# simple-loop-active4.net
KiCad netlist of a schematic drawn in EAGLE
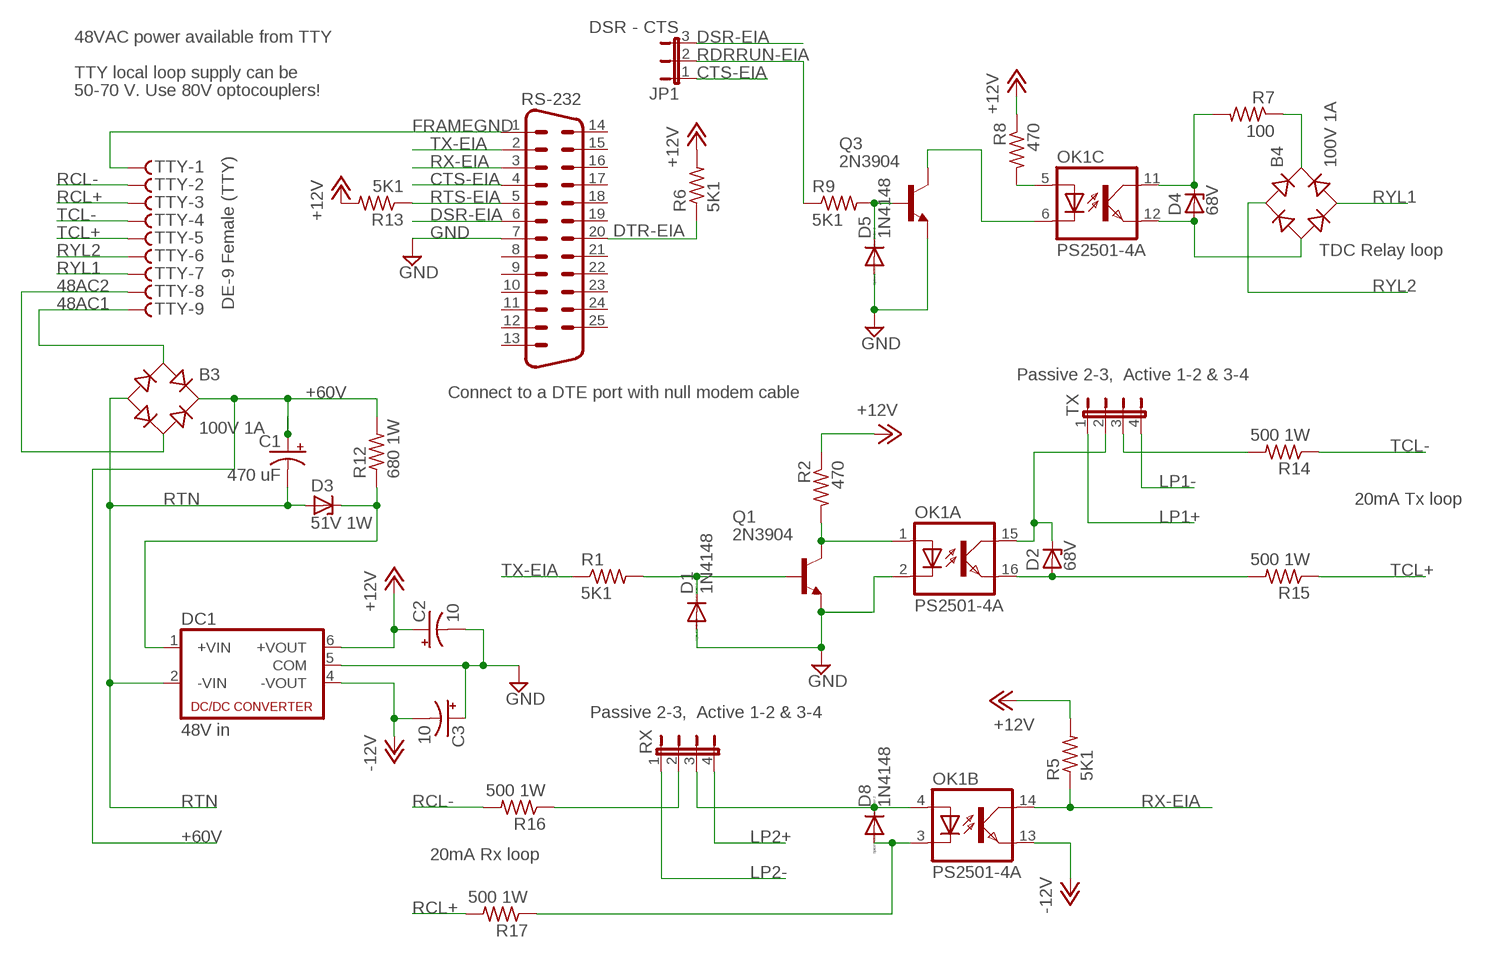
[diagram p0: schematic, sheet 1]
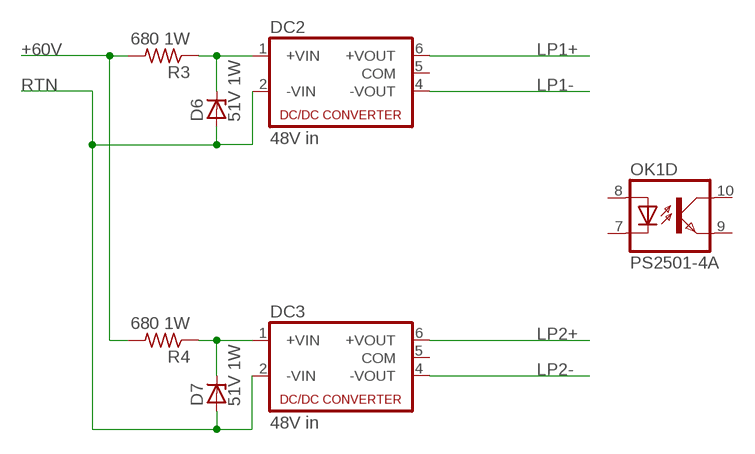
[diagram p1: schematic, sheet 2]

(export (version "E")
  (design (tool "Eeschema 10.0.6"))
  (components
    (comp (ref "D6")
      (value "51V 1W")
      (footprint "eagle-import:DO41Z10")
      (libsource (lib "eagle-import") (part "ZENER-DIODEDO41Z10"))
    )
    (comp (ref "D7")
      (value "51V 1W")
      (footprint "eagle-import:DO41Z10")
      (libsource (lib "eagle-import") (part "ZENER-DIODEDO41Z10"))
    )
    (comp (ref "DC2")
      (value "48V in")
      (footprint "eagle-import:NMA")
      (fields (field (name "MF") "C & D TECHNOLOGIES, INC") (field (name "MPN") "NMA0515SC"))
      (libsource (lib "eagle-import") (part "NMA"))
    )
    (comp (ref "DC3")
      (value "48V in")
      (footprint "eagle-import:NMA")
      (fields (field (name "MF") "C & D TECHNOLOGIES, INC") (field (name "MPN") "NMA0515SC"))
      (libsource (lib "eagle-import") (part "NMA"))
    )
    (comp (ref "OK1")
      (value "PS2501-4A")
      (footprint "eagle-import:DIL16")
      (fields (field (name "MF") "VISHAY/TELEFUNKEN") (field (name "MPN") "ILQ1"))
      (libsource (lib "eagle-import") (part "ILQ1"))
    )
    (comp (ref "R3")
      (value "680 1W")
      (footprint "eagle-import:P0817V")
      (libsource (lib "eagle-import") (part "R-US_0817/7V"))
    )
    (comp (ref "R4")
      (value "680 1W")
      (footprint "eagle-import:P0817V")
      (libsource (lib "eagle-import") (part "R-US_0817/7V"))
    )
    (comp (ref "B3")
      (value "100V 1A")
      (footprint "eagle-import:RB1A")
      (libsource (lib "eagle-import") (part "RB1A"))
    )
    (comp (ref "B4")
      (value "100V 1A")
      (footprint "eagle-import:RB1A")
      (libsource (lib "eagle-import") (part "RB1A"))
    )
    (comp (ref "C1")
      (value "470 uF")
      (footprint "eagle-import:E7,5-18")
      (libsource (lib "eagle-import") (part "CPOL-USE7.5-18"))
    )
    (comp (ref "C2")
      (value "10")
      (footprint "eagle-import:B45181A")
      (libsource (lib "eagle-import") (part "CPOL-USB45181A"))
    )
    (comp (ref "C3")
      (value "10")
      (footprint "eagle-import:B45181A")
      (libsource (lib "eagle-import") (part "CPOL-USB45181A"))
    )
    (comp (ref "D1")
      (value "1N4148")
      (footprint "eagle-import:DO35-10")
      (libsource (lib "eagle-import") (part "1N4148DO35-10"))
    )
    (comp (ref "D2")
      (value "68V")
      (footprint "eagle-import:DO41Z10")
      (libsource (lib "eagle-import") (part "ZENER-DIODEDO41Z10"))
    )
    (comp (ref "D3")
      (value "51V 1W")
      (footprint "eagle-import:DO41Z10")
      (libsource (lib "eagle-import") (part "ZENER-DIODEDO41Z10"))
    )
    (comp (ref "D4")
      (value "68V")
      (footprint "eagle-import:DO41Z10")
      (libsource (lib "eagle-import") (part "ZENER-DIODEDO41Z10"))
    )
    (comp (ref "D5")
      (value "1N4148")
      (footprint "eagle-import:DO35-10")
      (libsource (lib "eagle-import") (part "1N4148DO35-10"))
    )
    (comp (ref "D8")
      (value "1N4148")
      (footprint "eagle-import:DO35-10")
      (libsource (lib "eagle-import") (part "1N4148DO35-10"))
    )
    (comp (ref "DC1")
      (value "48V in")
      (footprint "eagle-import:NMA")
      (fields (field (name "MF") "C & D TECHNOLOGIES, INC") (field (name "MPN") "NMA0515SC"))
      (libsource (lib "eagle-import") (part "NMA"))
    )
    (comp (ref "JP1")
      (value "DSR - CTS")
      (footprint "eagle-import:JP2")
      (libsource (lib "eagle-import") (part "JP2E"))
    )
    (comp (ref "Q1")
      (value "2N3904")
      (footprint "eagle-import:TO92")
      (libsource (lib "eagle-import") (part "2N3904"))
    )
    (comp (ref "Q3")
      (value "2N3904")
      (footprint "eagle-import:TO92")
      (libsource (lib "eagle-import") (part "2N3904"))
    )
    (comp (ref "R1")
      (value "5K1")
      (footprint "eagle-import:0207_10")
      (libsource (lib "eagle-import") (part "R-US_0207/10"))
    )
    (comp (ref "R2")
      (value "470")
      (footprint "eagle-import:0207_10")
      (libsource (lib "eagle-import") (part "R-US_0207/10"))
    )
    (comp (ref "R5")
      (value "5K1")
      (footprint "eagle-import:0207_10")
      (libsource (lib "eagle-import") (part "R-US_0207/10"))
    )
    (comp (ref "R6")
      (value "5K1")
      (footprint "eagle-import:0207_10")
      (libsource (lib "eagle-import") (part "R-US_0207/10"))
    )
    (comp (ref "R7")
      (value "100")
      (footprint "eagle-import:0207_10")
      (libsource (lib "eagle-import") (part "R-US_0207/10"))
    )
    (comp (ref "R8")
      (value "470")
      (footprint "eagle-import:0207_10")
      (libsource (lib "eagle-import") (part "R-US_0207/10"))
    )
    (comp (ref "R9")
      (value "5K1")
      (footprint "eagle-import:0207_10")
      (libsource (lib "eagle-import") (part "R-US_0207/10"))
    )
    (comp (ref "R12")
      (value "680 1W")
      (footprint "eagle-import:P0817V")
      (libsource (lib "eagle-import") (part "R-US_0817/7V"))
    )
    (comp (ref "R13")
      (value "5K1")
      (footprint "eagle-import:0207_10")
      (libsource (lib "eagle-import") (part "R-US_0207/10"))
    )
    (comp (ref "R14")
      (value "500 1W")
      (footprint "eagle-import:P0817V")
      (libsource (lib "eagle-import") (part "R-US_0817/7V"))
    )
    (comp (ref "R15")
      (value "500 1W")
      (footprint "eagle-import:P0817V")
      (libsource (lib "eagle-import") (part "R-US_0817/7V"))
    )
    (comp (ref "R16")
      (value "500 1W")
      (footprint "eagle-import:P0817V")
      (libsource (lib "eagle-import") (part "R-US_0817/7V"))
    )
    (comp (ref "R17")
      (value "500 1W")
      (footprint "eagle-import:P0817V")
      (libsource (lib "eagle-import") (part "R-US_0817/7V"))
    )
    (comp (ref "RS-232")
      (value "M25H")
      (footprint "eagle-import:M25H")
      (libsource (lib "eagle-import") (part "M25H"))
    )
    (comp (ref "RX")
      (value "JP4E")
      (footprint "eagle-import:JP4")
      (libsource (lib "eagle-import") (part "JP4E"))
    )
    (comp (ref "TTY")
      (value "F09HS")
      (footprint "eagle-import:F09H")
      (libsource (lib "eagle-import") (part "F09?SH"))
    )
    (comp (ref "TX")
      (value "JP4E")
      (footprint "eagle-import:JP4")
      (libsource (lib "eagle-import") (part "JP4E"))
    )
  )
  (nets
    (net (code "1") (name "+12V") (class "Default")
      (node (ref "C2") (pin "+") (pinfunction "+_+") (pintype "passive"))
      (node (ref "DC1") (pin "6") (pinfunction "+VOUT_6") (pintype "passive"))
      (node (ref "R13") (pin "2") (pinfunction "2_2") (pintype "passive"))
      (node (ref "R2") (pin "1") (pinfunction "1_1") (pintype "passive"))
      (node (ref "R5") (pin "2") (pinfunction "2_2") (pintype "passive"))
      (node (ref "R6") (pin "2") (pinfunction "2_2") (pintype "passive"))
      (node (ref "R8") (pin "1") (pinfunction "1_1") (pintype "passive"))
    )
    (net (code "2") (name "+60V") (class "Default")
      (node (ref "B3") (pin "+") (pinfunction "+_+") (pintype "passive"))
      (node (ref "C1") (pin "+") (pinfunction "+_+") (pintype "passive"))
      (node (ref "R12") (pin "2") (pinfunction "2_2") (pintype "passive"))
      (node (ref "R3") (pin "2") (pinfunction "2_2") (pintype "passive"))
      (node (ref "R4") (pin "2") (pinfunction "2_2") (pintype "passive"))
    )
    (net (code "3") (name "-12V") (class "Default")
      (node (ref "C3") (pin "-") (pinfunction "-_-") (pintype "passive"))
      (node (ref "DC1") (pin "4") (pinfunction "-VOUT_4") (pintype "passive"))
      (node (ref "OK1") (pin "13") (pinfunction "EMIT_13") (pintype "passive"))
    )
    (net (code "4") (name "48AC1") (class "Default")
      (node (ref "B3") (pin "AC1") (pinfunction "AC1_AC1") (pintype "passive"))
      (node (ref "TTY") (pin "9") (pinfunction "F_9") (pintype "passive"))
    )
    (net (code "5") (name "48AC2") (class "Default")
      (node (ref "B3") (pin "AC2") (pinfunction "AC2_AC2") (pintype "passive"))
      (node (ref "TTY") (pin "8") (pinfunction "F_8") (pintype "passive"))
    )
    (net (code "6") (name "CTS-EIA") (class "Default")
      (node (ref "JP1") (pin "1") (pinfunction "1_1") (pintype "passive"))
      (node (ref "RS-232") (pin "4") (pinfunction "4_4") (pintype "passive"))
    )
    (net (code "7") (name "DSR-EIA") (class "Default")
      (node (ref "JP1") (pin "3") (pinfunction "3_3") (pintype "passive"))
      (node (ref "RS-232") (pin "6") (pinfunction "6_6") (pintype "passive"))
    )
    (net (code "8") (name "DTR-EIA") (class "Default")
      (node (ref "R6") (pin "1") (pinfunction "1_1") (pintype "passive"))
      (node (ref "RS-232") (pin "20") (pinfunction "20_20") (pintype "passive"))
    )
    (net (code "9") (name "FRAMEGND") (class "Default")
      (node (ref "RS-232") (pin "1") (pinfunction "1_1") (pintype "passive"))
      (node (ref "TTY") (pin "1") (pinfunction "F_1") (pintype "passive"))
    )
    (net (code "10") (name "GND") (class "Default")
      (node (ref "C2") (pin "-") (pinfunction "-_-") (pintype "passive"))
      (node (ref "C3") (pin "+") (pinfunction "+_+") (pintype "passive"))
      (node (ref "D1") (pin "A") (pinfunction "A_A") (pintype "passive"))
      (node (ref "D5") (pin "A") (pinfunction "A_A") (pintype "passive"))
      (node (ref "DC1") (pin "5") (pinfunction "COM_5") (pintype "passive"))
      (node (ref "OK1") (pin "2") (pinfunction "C_2") (pintype "passive"))
      (node (ref "Q1") (pin "3") (pinfunction "E_3") (pintype "passive"))
      (node (ref "Q3") (pin "3") (pinfunction "E_3") (pintype "passive"))
      (node (ref "RS-232") (pin "7") (pinfunction "7_7") (pintype "passive"))
    )
    (net (code "11") (name "LP1+") (class "Default")
      (node (ref "DC2") (pin "6") (pinfunction "+VOUT_6") (pintype "passive"))
      (node (ref "TX") (pin "1") (pinfunction "1_1") (pintype "passive"))
    )
    (net (code "12") (name "LP1-") (class "Default")
      (node (ref "DC2") (pin "4") (pinfunction "-VOUT_4") (pintype "passive"))
      (node (ref "TX") (pin "4") (pinfunction "4_4") (pintype "passive"))
    )
    (net (code "13") (name "LP2+") (class "Default")
      (node (ref "DC3") (pin "6") (pinfunction "+VOUT_6") (pintype "passive"))
      (node (ref "RX") (pin "4") (pinfunction "4_4") (pintype "passive"))
    )
    (net (code "14") (name "LP2-") (class "Default")
      (node (ref "DC3") (pin "4") (pinfunction "-VOUT_4") (pintype "passive"))
      (node (ref "RX") (pin "1") (pinfunction "1_1") (pintype "passive"))
    )
    (net (code "15") (name "Net-(B4-Pad+)") (class "Default")
      (node (ref "B4") (pin "+") (pinfunction "+_+") (pintype "passive"))
      (node (ref "R7") (pin "1") (pinfunction "1_1") (pintype "passive"))
    )
    (net (code "16") (name "Net-(DC1-+VIN)") (class "Default")
      (node (ref "D3") (pin "C") (pinfunction "C_C") (pintype "passive"))
      (node (ref "DC1") (pin "1") (pinfunction "+VIN_1") (pintype "passive"))
      (node (ref "R12") (pin "1") (pinfunction "1_1") (pintype "passive"))
    )
    (net (code "17") (name "Net-(DC2-+VIN)") (class "Default")
      (node (ref "D6") (pin "C") (pinfunction "C_C") (pintype "passive"))
      (node (ref "DC2") (pin "1") (pinfunction "+VIN_1") (pintype "passive"))
      (node (ref "R3") (pin "1") (pinfunction "1_1") (pintype "passive"))
    )
    (net (code "18") (name "Net-(DC3-+VIN)") (class "Default")
      (node (ref "D7") (pin "C") (pinfunction "C_C") (pintype "passive"))
      (node (ref "DC3") (pin "1") (pinfunction "+VIN_1") (pintype "passive"))
      (node (ref "R4") (pin "1") (pinfunction "1_1") (pintype "passive"))
    )
    (net (code "19") (name "Net-(OK1A-A)") (class "Default")
      (node (ref "OK1") (pin "1") (pinfunction "A_1") (pintype "passive"))
      (node (ref "Q1") (pin "1") (pinfunction "C_1") (pintype "passive"))
      (node (ref "R2") (pin "2") (pinfunction "2_2") (pintype "passive"))
    )
    (net (code "20") (name "Net-(OK1A-COL)") (class "Default")
      (node (ref "D2") (pin "C") (pinfunction "C_C") (pintype "passive"))
      (node (ref "OK1") (pin "15") (pinfunction "COL_15") (pintype "passive"))
      (node (ref "TX") (pin "2") (pinfunction "2_2") (pintype "passive"))
    )
    (net (code "21") (name "Net-(OK1A-EMIT)") (class "Default")
      (node (ref "D2") (pin "A") (pinfunction "A_A") (pintype "passive"))
      (node (ref "OK1") (pin "16") (pinfunction "EMIT_16") (pintype "passive"))
      (node (ref "R15") (pin "2") (pinfunction "2_2") (pintype "passive"))
    )
    (net (code "22") (name "Net-(OK1B-A)") (class "Default")
      (node (ref "D8") (pin "C") (pinfunction "C_C") (pintype "passive"))
      (node (ref "OK1") (pin "4") (pinfunction "A_4") (pintype "passive"))
      (node (ref "RX") (pin "3") (pinfunction "3_3") (pintype "passive"))
    )
    (net (code "23") (name "Net-(OK1B-C)") (class "Default")
      (node (ref "D8") (pin "A") (pinfunction "A_A") (pintype "passive"))
      (node (ref "OK1") (pin "3") (pinfunction "C_3") (pintype "passive"))
      (node (ref "R17") (pin "1") (pinfunction "1_1") (pintype "passive"))
    )
    (net (code "24") (name "Net-(OK1C-A)") (class "Default")
      (node (ref "OK1") (pin "5") (pinfunction "A_5") (pintype "passive"))
      (node (ref "R8") (pin "2") (pinfunction "2_2") (pintype "passive"))
    )
    (net (code "25") (name "Net-(OK1C-C)") (class "Default")
      (node (ref "OK1") (pin "6") (pinfunction "C_6") (pintype "passive"))
      (node (ref "Q3") (pin "1") (pinfunction "C_1") (pintype "passive"))
    )
    (net (code "26") (name "Net-(OK1C-COL)") (class "Default")
      (node (ref "D4") (pin "C") (pinfunction "C_C") (pintype "passive"))
      (node (ref "OK1") (pin "11") (pinfunction "COL_11") (pintype "passive"))
      (node (ref "R7") (pin "2") (pinfunction "2_2") (pintype "passive"))
    )
    (net (code "27") (name "Net-(OK1C-EMIT)") (class "Default")
      (node (ref "B4") (pin "-") (pinfunction "-_-") (pintype "passive"))
      (node (ref "D4") (pin "A") (pinfunction "A_A") (pintype "passive"))
      (node (ref "OK1") (pin "12") (pinfunction "EMIT_12") (pintype "passive"))
    )
    (net (code "28") (name "Net-(Q1-B)") (class "Default")
      (node (ref "D1") (pin "C") (pinfunction "C_C") (pintype "passive"))
      (node (ref "Q1") (pin "2") (pinfunction "B_2") (pintype "passive"))
      (node (ref "R1") (pin "2") (pinfunction "2_2") (pintype "passive"))
    )
    (net (code "29") (name "Net-(Q3-B)") (class "Default")
      (node (ref "D5") (pin "C") (pinfunction "C_C") (pintype "passive"))
      (node (ref "Q3") (pin "2") (pinfunction "B_2") (pintype "passive"))
      (node (ref "R9") (pin "2") (pinfunction "2_2") (pintype "passive"))
    )
    (net (code "30") (name "Net-(R14-Pad2)") (class "Default")
      (node (ref "R14") (pin "2") (pinfunction "2_2") (pintype "passive"))
      (node (ref "TX") (pin "3") (pinfunction "3_3") (pintype "passive"))
    )
    (net (code "31") (name "Net-(R16-Pad1)") (class "Default")
      (node (ref "R16") (pin "1") (pinfunction "1_1") (pintype "passive"))
      (node (ref "RX") (pin "2") (pinfunction "2_2") (pintype "passive"))
    )
    (net (code "32") (name "RCL+") (class "Default")
      (node (ref "R17") (pin "2") (pinfunction "2_2") (pintype "passive"))
      (node (ref "TTY") (pin "3") (pinfunction "F_3") (pintype "passive"))
    )
    (net (code "33") (name "RCL-") (class "Default")
      (node (ref "R16") (pin "2") (pinfunction "2_2") (pintype "passive"))
      (node (ref "TTY") (pin "2") (pinfunction "F_2") (pintype "passive"))
    )
    (net (code "34") (name "RDRRUN-EIA") (class "Default")
      (node (ref "JP1") (pin "2") (pinfunction "2_2") (pintype "passive"))
      (node (ref "R9") (pin "1") (pinfunction "1_1") (pintype "passive"))
    )
    (net (code "35") (name "RTN") (class "Default")
      (node (ref "B3") (pin "-") (pinfunction "-_-") (pintype "passive"))
      (node (ref "C1") (pin "-") (pinfunction "-_-") (pintype "passive"))
      (node (ref "D3") (pin "A") (pinfunction "A_A") (pintype "passive"))
      (node (ref "D6") (pin "A") (pinfunction "A_A") (pintype "passive"))
      (node (ref "D7") (pin "A") (pinfunction "A_A") (pintype "passive"))
      (node (ref "DC1") (pin "2") (pinfunction "-VIN_2") (pintype "passive"))
      (node (ref "DC2") (pin "2") (pinfunction "-VIN_2") (pintype "passive"))
      (node (ref "DC3") (pin "2") (pinfunction "-VIN_2") (pintype "passive"))
    )
    (net (code "36") (name "RTS-EIA") (class "Default")
      (node (ref "R13") (pin "1") (pinfunction "1_1") (pintype "passive"))
      (node (ref "RS-232") (pin "5") (pinfunction "5_5") (pintype "passive"))
    )
    (net (code "37") (name "RX-EIA") (class "Default")
      (node (ref "OK1") (pin "14") (pinfunction "COL_14") (pintype "passive"))
      (node (ref "R5") (pin "1") (pinfunction "1_1") (pintype "passive"))
      (node (ref "RS-232") (pin "3") (pinfunction "3_3") (pintype "passive"))
    )
    (net (code "38") (name "RYL1") (class "Default")
      (node (ref "B4") (pin "AC2") (pinfunction "AC2_AC2") (pintype "passive"))
      (node (ref "TTY") (pin "7") (pinfunction "F_7") (pintype "passive"))
    )
    (net (code "39") (name "RYL2") (class "Default")
      (node (ref "B4") (pin "AC1") (pinfunction "AC1_AC1") (pintype "passive"))
      (node (ref "TTY") (pin "6") (pinfunction "F_6") (pintype "passive"))
    )
    (net (code "40") (name "TCL+") (class "Default")
      (node (ref "R15") (pin "1") (pinfunction "1_1") (pintype "passive"))
      (node (ref "TTY") (pin "5") (pinfunction "F_5") (pintype "passive"))
    )
    (net (code "41") (name "TCL-") (class "Default")
      (node (ref "R14") (pin "1") (pinfunction "1_1") (pintype "passive"))
      (node (ref "TTY") (pin "4") (pinfunction "F_4") (pintype "passive"))
    )
    (net (code "42") (name "TX-EIA") (class "Default")
      (node (ref "R1") (pin "1") (pinfunction "1_1") (pintype "passive"))
      (node (ref "RS-232") (pin "2") (pinfunction "2_2") (pintype "passive"))
    )
    (net (code "43") (name "unconnected-(DC2-COM-Pad5)") (class "Default")
      (node (ref "DC2") (pin "5") (pinfunction "COM_5") (pintype "passive"))
    )
    (net (code "44") (name "unconnected-(DC3-COM-Pad5)") (class "Default")
      (node (ref "DC3") (pin "5") (pinfunction "COM_5") (pintype "passive"))
    )
    (net (code "45") (name "unconnected-(OK1D-A-Pad8)") (class "Default")
      (node (ref "OK1") (pin "8") (pinfunction "A_8") (pintype "passive"))
    )
    (net (code "46") (name "unconnected-(OK1D-C-Pad7)") (class "Default")
      (node (ref "OK1") (pin "7") (pinfunction "C_7") (pintype "passive"))
    )
    (net (code "47") (name "unconnected-(OK1D-COL-Pad10)") (class "Default")
      (node (ref "OK1") (pin "10") (pinfunction "COL_10") (pintype "passive"))
    )
    (net (code "48") (name "unconnected-(OK1D-EMIT-Pad9)") (class "Default")
      (node (ref "OK1") (pin "9") (pinfunction "EMIT_9") (pintype "passive"))
    )
    (net (code "49") (name "unconnected-(RS-232-Pad8)") (class "Default")
      (node (ref "RS-232") (pin "8") (pinfunction "8_8") (pintype "passive"))
    )
    (net (code "50") (name "unconnected-(RS-232-Pad9)") (class "Default")
      (node (ref "RS-232") (pin "9") (pinfunction "9_9") (pintype "passive"))
    )
    (net (code "51") (name "unconnected-(RS-232-Pad10)") (class "Default")
      (node (ref "RS-232") (pin "10") (pinfunction "10_10") (pintype "passive"))
    )
    (net (code "52") (name "unconnected-(RS-232-Pad11)") (class "Default")
      (node (ref "RS-232") (pin "11") (pinfunction "11_11") (pintype "passive"))
    )
    (net (code "53") (name "unconnected-(RS-232-Pad12)") (class "Default")
      (node (ref "RS-232") (pin "12") (pinfunction "12_12") (pintype "passive"))
    )
    (net (code "54") (name "unconnected-(RS-232-Pad13)") (class "Default")
      (node (ref "RS-232") (pin "13") (pinfunction "13_13") (pintype "passive"))
    )
    (net (code "55") (name "unconnected-(RS-232-Pad14)") (class "Default")
      (node (ref "RS-232") (pin "14") (pinfunction "14_14") (pintype "passive"))
    )
    (net (code "56") (name "unconnected-(RS-232-Pad15)") (class "Default")
      (node (ref "RS-232") (pin "15") (pinfunction "15_15") (pintype "passive"))
    )
    (net (code "57") (name "unconnected-(RS-232-Pad16)") (class "Default")
      (node (ref "RS-232") (pin "16") (pinfunction "16_16") (pintype "passive"))
    )
    (net (code "58") (name "unconnected-(RS-232-Pad17)") (class "Default")
      (node (ref "RS-232") (pin "17") (pinfunction "17_17") (pintype "passive"))
    )
    (net (code "59") (name "unconnected-(RS-232-Pad18)") (class "Default")
      (node (ref "RS-232") (pin "18") (pinfunction "18_18") (pintype "passive"))
    )
    (net (code "60") (name "unconnected-(RS-232-Pad19)") (class "Default")
      (node (ref "RS-232") (pin "19") (pinfunction "19_19") (pintype "passive"))
    )
    (net (code "61") (name "unconnected-(RS-232-Pad21)") (class "Default")
      (node (ref "RS-232") (pin "21") (pinfunction "21_21") (pintype "passive"))
    )
    (net (code "62") (name "unconnected-(RS-232-Pad22)") (class "Default")
      (node (ref "RS-232") (pin "22") (pinfunction "22_22") (pintype "passive"))
    )
    (net (code "63") (name "unconnected-(RS-232-Pad23)") (class "Default")
      (node (ref "RS-232") (pin "23") (pinfunction "23_23") (pintype "passive"))
    )
    (net (code "64") (name "unconnected-(RS-232-Pad24)") (class "Default")
      (node (ref "RS-232") (pin "24") (pinfunction "24_24") (pintype "passive"))
    )
    (net (code "65") (name "unconnected-(RS-232-Pad25)") (class "Default")
      (node (ref "RS-232") (pin "25") (pinfunction "25_25") (pintype "passive"))
    )
  )
)
